# adc_mcp3914.net
KiCad netlist of a schematic drawn in Altium Designer
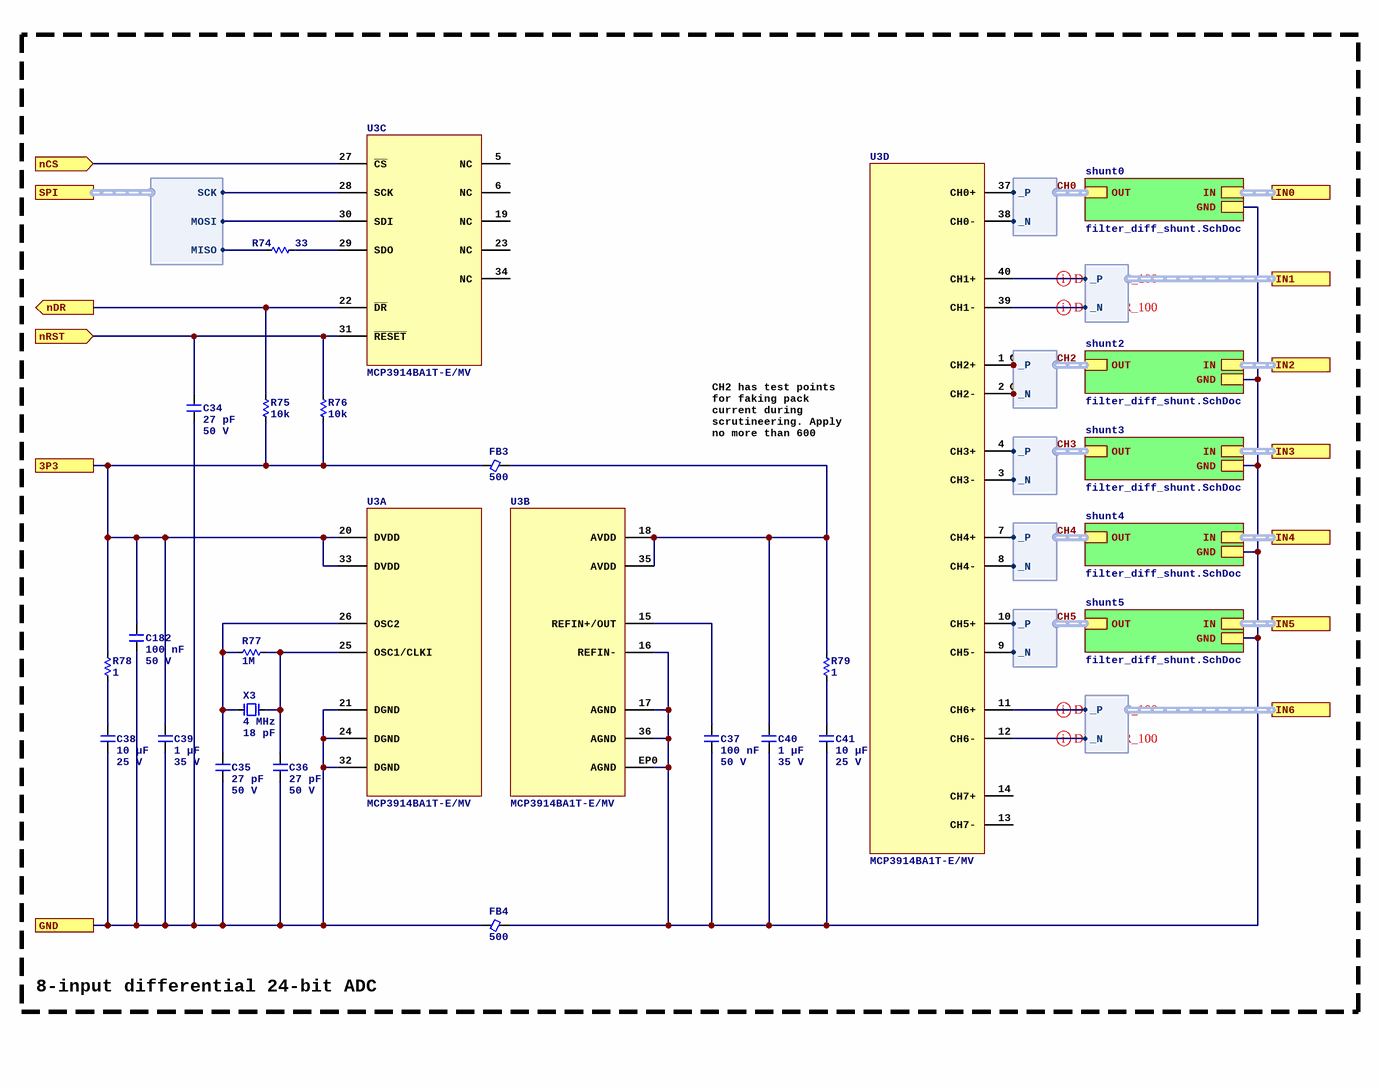
[diagram p0: adc_mcp3914.SchDoc]

(export (version "E")
  (design (tool "Eeschema 10.0.6"))
  (components
    (comp (ref "C34")
      (value "0402CG270J500NT")
      (footprint "C0402")
      (fields
        (field (name "CAPACITANCE") "27 pF")
        (field (name "MANUFACTURER") "FH(Guangdong Fenghua Advanced Tech)")
        (field (name "VOLTAGE RATING") "50 V")
      )
      (libsource (lib "database") (part "__template_cap"))
    )
    (comp (ref "C35")
      (value "0402CG270J500NT")
      (footprint "C0402")
      (fields
        (field (name "CAPACITANCE") "27 pF")
        (field (name "MANUFACTURER") "FH(Guangdong Fenghua Advanced Tech)")
        (field (name "VOLTAGE RATING") "50 V")
      )
      (libsource (lib "database") (part "__template_cap"))
    )
    (comp (ref "C36")
      (value "0402CG270J500NT")
      (footprint "C0402")
      (fields
        (field (name "CAPACITANCE") "27 pF")
        (field (name "MANUFACTURER") "FH(Guangdong Fenghua Advanced Tech)")
        (field (name "VOLTAGE RATING") "50 V")
      )
      (libsource (lib "database") (part "__template_cap"))
    )
    (comp (ref "C37")
      (value "CL05B104KB54PNC")
      (footprint "C0402")
      (fields
        (field (name "CAPACITANCE") "100 nF")
        (field (name "MANUFACTURER") "Samsung Electro-Mechanics")
        (field (name "VOLTAGE RATING") "50 V")
      )
      (libsource (lib "database") (part "__template_cap"))
    )
    (comp (ref "C38")
      (value "CL21B106KAYQNNE")
      (footprint "C0805")
      (fields
        (field (name "CAPACITANCE") "10 µF")
        (field (name "MANUFACTURER") "Samsung Electro-Mechanics")
        (field (name "VOLTAGE RATING") "25 V")
      )
      (libsource (lib "database") (part "__template_cap"))
    )
    (comp (ref "C39")
      (value "GMK107AB7105KAHT")
      (footprint "C0603")
      (fields
        (field (name "CAPACITANCE") "1 µF")
        (field (name "MANUFACTURER") "Taiyo Yuden")
        (field (name "VOLTAGE RATING") "35 V")
      )
      (libsource (lib "database") (part "__template_cap"))
    )
    (comp (ref "C40")
      (value "GMK107AB7105KAHT")
      (footprint "C0603")
      (fields
        (field (name "CAPACITANCE") "1 µF")
        (field (name "MANUFACTURER") "Taiyo Yuden")
        (field (name "VOLTAGE RATING") "35 V")
      )
      (libsource (lib "database") (part "__template_cap"))
    )
    (comp (ref "C41")
      (value "CL21B106KAYQNNE")
      (footprint "C0805")
      (fields
        (field (name "CAPACITANCE") "10 µF")
        (field (name "MANUFACTURER") "Samsung Electro-Mechanics")
        (field (name "VOLTAGE RATING") "25 V")
      )
      (libsource (lib "database") (part "__template_cap"))
    )
    (comp (ref "C182")
      (value "CL05B104KB54PNC")
      (footprint "C0402")
      (fields
        (field (name "CAPACITANCE") "100 nF")
        (field (name "MANUFACTURER") "Samsung Electro-Mechanics")
        (field (name "VOLTAGE RATING") "50 V")
      )
      (libsource (lib "database") (part "__template_cap"))
    )
    (comp (ref "FB3")
      (value "BLM15AX601SN1D")
      (footprint "FB0402")
      (fields (field (name "MANUFACTURER") "Murata Electronics") (field (name "CURRENT RATING (MA)") "500"))
      (libsource (lib "database") (part "__template_fb"))
    )
    (comp (ref "FB4")
      (value "BLM15AX601SN1D")
      (footprint "FB0402")
      (fields (field (name "MANUFACTURER") "Murata Electronics") (field (name "CURRENT RATING (MA)") "500"))
      (libsource (lib "database") (part "__template_fb"))
    )
    (comp (ref "R74")
      (value "33")
      (footprint "R0402")
      (fields
        (field (name "TOLERANCE") "1%")
        (field (name "MANUFACTURER PART NUMBER") "0402WGF330JTCE")
        (field (name "MANUFACTURER") "UNI-ROYAL(Uniroyal Elec)")
      )
      (libsource (lib "database") (part "__template_resistor"))
    )
    (comp (ref "R75")
      (value "10k")
      (footprint "R0402")
      (fields
        (field (name "TOLERANCE") "1%")
        (field (name "MANUFACTURER PART NUMBER") "0402WGF1002TCE")
        (field (name "MANUFACTURER") "UNI-ROYAL(Uniroyal Elec)")
      )
      (libsource (lib "database") (part "__template_resistor"))
    )
    (comp (ref "R76")
      (value "10k")
      (footprint "R0402")
      (fields
        (field (name "TOLERANCE") "1%")
        (field (name "MANUFACTURER PART NUMBER") "0402WGF1002TCE")
        (field (name "MANUFACTURER") "UNI-ROYAL(Uniroyal Elec)")
      )
      (libsource (lib "database") (part "__template_resistor"))
    )
    (comp (ref "R77")
      (value "1M")
      (footprint "R0402")
      (fields
        (field (name "TOLERANCE") "1%")
        (field (name "MANUFACTURER PART NUMBER") "0402WGF1004TCE")
        (field (name "MANUFACTURER") "UNI-ROYAL(Uniroyal Elec)")
      )
      (libsource (lib "database") (part "__template_resistor"))
    )
    (comp (ref "R78")
      (value "1")
      (footprint "R0402")
      (fields
        (field (name "TOLERANCE") "1%")
        (field (name "MANUFACTURER PART NUMBER") "CRCW04021R00FKED")
        (field (name "MANUFACTURER") "Vishay Intertech")
      )
      (libsource (lib "database") (part "__template_resistor"))
    )
    (comp (ref "R79")
      (value "1")
      (footprint "R0402")
      (fields
        (field (name "TOLERANCE") "1%")
        (field (name "MANUFACTURER PART NUMBER") "CRCW04021R00FKED")
        (field (name "MANUFACTURER") "Vishay Intertech")
      )
      (libsource (lib "database") (part "__template_resistor"))
    )
    (comp (ref "TP71")
      (value "RH-5000")
      (footprint "TP_RH-5000")
      (description "Red through-hole PCB test point")
      (fields (field (name "MANUFACTURER") "ronghe"))
      (libsource (lib "database") (part "__template_testpoint"))
    )
    (comp (ref "TP72")
      (value "RH-5001")
      (footprint "TP_RH-5001")
      (description "Black through-hole PCB test point")
      (fields (field (name "MANUFACTURER") "ronghe"))
      (libsource (lib "database") (part "__template_testpoint"))
    )
    (comp (ref "U3")
      (value "MCP3914BA1T-E/MV")
      (footprint "MICROCHIP_MV")
      (description "8 Channel AFE 24 Bit 40-UQFN (5x5)")
      (fields (field (name "MANUFACTURER") "Microchip"))
      (libsource (lib "") (part "MCP3914BA1T-E/MV_1"))
    )
    (comp (ref "X3")
      (value "ABLS2-4.000MHZ-D4Y-T")
      (footprint "XTAL_HC49US_SMD")
      (description "CRYSTAL 4.000 MHZ 18PF SMD")
      (fields
        (field (name "MANUFACTURER") "Abracon LLC")
        (field (name "FREQUENCY") "4 MHz")
        (field (name "CAPACITANCE") "18 pF")
      )
      (libsource (lib "database") (part "__template_crystal_2pin"))
    )
  )
  (nets
    (net (code "13") (name "/3P3") (class "Default")
      (node (ref "C182") (pin "1") (pintype "passive"))
      (node (ref "C39") (pin "1") (pintype "passive"))
      (node (ref "FB3") (pin "1") (pintype "passive"))
      (node (ref "R75") (pin "2") (pintype "passive"))
      (node (ref "R76") (pin "2") (pintype "passive"))
      (node (ref "R78") (pin "2") (pintype "passive"))
      (node (ref "U3") (pin "20") (pinfunction "DVDD_20") (pintype "passive"))
      (node (ref "U3") (pin "33") (pinfunction "DVDD_33") (pintype "passive"))
    )
    (net (code "19") (name "/GND") (class "Default")
      (node (ref "C182") (pin "2") (pintype "passive"))
      (node (ref "C34") (pin "2") (pintype "passive"))
      (node (ref "C35") (pin "2") (pintype "passive"))
      (node (ref "C36") (pin "2") (pintype "passive"))
      (node (ref "C38") (pin "2") (pintype "passive"))
      (node (ref "C39") (pin "2") (pintype "passive"))
      (node (ref "FB4") (pin "1") (pintype "passive"))
      (node (ref "U3") (pin "21") (pinfunction "DGND_21") (pintype "passive"))
      (node (ref "U3") (pin "24") (pinfunction "DGND_24") (pintype "passive"))
      (node (ref "U3") (pin "32") (pinfunction "DGND_32") (pintype "passive"))
    )
    (net (code "20") (name "/GND_1") (class "Default")
      (node (ref "C37") (pin "2") (pintype "passive"))
      (node (ref "C40") (pin "2") (pintype "passive"))
      (node (ref "C41") (pin "2") (pintype "passive"))
      (node (ref "FB4") (pin "2") (pintype "passive"))
      (node (ref "U3") (pin "16") (pinfunction "REFIN-_16") (pintype "passive"))
      (node (ref "U3") (pin "17") (pinfunction "AGND_17") (pintype "passive"))
      (node (ref "U3") (pin "36") (pinfunction "AGND_36") (pintype "passive"))
      (node (ref "U3") (pin "EP0") (pinfunction "AGND_EP0") (pintype "passive"))
    )
    (net (code "26") (name "/MISO") (class "Default") (node (ref "R74") (pin "2") (pintype "passive")))
    (net (code "27") (name "/MOSI") (class "Default")
      (node (ref "U3") (pin "30") (pinfunction "SDI_30") (pintype "passive"))
    )
    (net (code "28") (name "/SCK") (class "Default")
      (node (ref "U3") (pin "28") (pinfunction "SCK_28") (pintype "passive"))
    )
    (net (code "29") (name "/nCS") (class "Default")
      (node (ref "U3") (pin "27") (pinfunction "~{CS}_27") (pintype "passive"))
    )
    (net (code "30") (name "/nDR") (class "Default")
      (node (ref "R75") (pin "1") (pintype "passive"))
      (node (ref "U3") (pin "22") (pinfunction "~{DR}_22") (pintype "passive"))
    )
    (net (code "31") (name "/nRST") (class "Default")
      (node (ref "C34") (pin "1") (pintype "passive"))
      (node (ref "R76") (pin "1") (pintype "passive"))
      (node (ref "U3") (pin "31") (pinfunction "~{RESET}_31") (pintype "passive"))
    )
    (net (code "34") (name "Net-(C38-Pad1)") (class "Default")
      (node (ref "C38") (pin "1") (pintype "passive"))
      (node (ref "R78") (pin "1") (pintype "passive"))
    )
    (net (code "35") (name "Net-(C40-Pad1)") (class "Default")
      (node (ref "C40") (pin "1") (pintype "passive"))
      (node (ref "FB3") (pin "2") (pintype "passive"))
      (node (ref "R79") (pin "2") (pintype "passive"))
      (node (ref "U3") (pin "18") (pinfunction "AVDD_18") (pintype "passive"))
      (node (ref "U3") (pin "35") (pinfunction "AVDD_35") (pintype "passive"))
    )
    (net (code "36") (name "Net-(C41-Pad1)") (class "Default")
      (node (ref "C41") (pin "1") (pintype "passive"))
      (node (ref "R79") (pin "1") (pintype "passive"))
    )
    (net (code "37") (name "Net-(U3A-OSC1{slash}CLKI)") (class "Default")
      (node (ref "C36") (pin "1") (pintype "passive"))
      (node (ref "R77") (pin "1") (pintype "passive"))
      (node (ref "U3") (pin "25") (pinfunction "OSC1/CLKI_25") (pintype "passive"))
      (node (ref "X3") (pin "1") (pinfunction "1_1") (pintype "passive"))
    )
    (net (code "38") (name "Net-(U3A-OSC2)") (class "Default")
      (node (ref "C35") (pin "1") (pintype "passive"))
      (node (ref "R77") (pin "2") (pintype "passive"))
      (node (ref "U3") (pin "26") (pinfunction "OSC2_26") (pintype "passive"))
      (node (ref "X3") (pin "2") (pinfunction "2_2") (pintype "passive"))
    )
    (net (code "39") (name "Net-(U3B-REFIN+{slash}OUT)") (class "Default")
      (node (ref "C37") (pin "1") (pintype "passive"))
      (node (ref "U3") (pin "15") (pinfunction "REFIN+/OUT_15") (pintype "passive"))
    )
    (net (code "40") (name "Net-(U3C-SDO)") (class "Default")
      (node (ref "R74") (pin "1") (pintype "passive"))
      (node (ref "U3") (pin "29") (pinfunction "SDO_29") (pintype "passive"))
    )
    (net (code "41") (name "Net-(U3D-CH2+)") (class "Default")
      (node (ref "TP71") (pin "1") (pintype "passive"))
      (node (ref "U3") (pin "1") (pinfunction "CH2+_1") (pintype "passive"))
    )
    (net (code "42") (name "Net-(U3D-CH2-)") (class "Default")
      (node (ref "TP72") (pin "1") (pintype "passive"))
      (node (ref "U3") (pin "2") (pinfunction "CH2-_2") (pintype "passive"))
    )
    (net (code "43") (name "unconnected-(U3C-NC-Pad5)") (class "Default")
      (node (ref "U3") (pin "5") (pinfunction "NC_5") (pintype "passive"))
    )
    (net (code "44") (name "unconnected-(U3C-NC-Pad6)") (class "Default")
      (node (ref "U3") (pin "6") (pinfunction "NC_6") (pintype "passive"))
    )
    (net (code "45") (name "unconnected-(U3C-NC-Pad19)") (class "Default")
      (node (ref "U3") (pin "19") (pinfunction "NC_19") (pintype "passive"))
    )
    (net (code "46") (name "unconnected-(U3C-NC-Pad23)") (class "Default")
      (node (ref "U3") (pin "23") (pinfunction "NC_23") (pintype "passive"))
    )
    (net (code "47") (name "unconnected-(U3C-NC-Pad34)") (class "Default")
      (node (ref "U3") (pin "34") (pinfunction "NC_34") (pintype "passive"))
    )
    (net (code "48") (name "unconnected-(U3D-CH0+-Pad37)") (class "Default")
      (node (ref "U3") (pin "37") (pinfunction "CH0+_37") (pintype "passive"))
    )
    (net (code "49") (name "unconnected-(U3D-CH0--Pad38)") (class "Default")
      (node (ref "U3") (pin "38") (pinfunction "CH0-_38") (pintype "passive"))
    )
    (net (code "50") (name "unconnected-(U3D-CH1+-Pad40)") (class "Default")
      (node (ref "U3") (pin "40") (pinfunction "CH1+_40") (pintype "passive"))
    )
    (net (code "51") (name "unconnected-(U3D-CH1--Pad39)") (class "Default")
      (node (ref "U3") (pin "39") (pinfunction "CH1-_39") (pintype "passive"))
    )
    (net (code "52") (name "unconnected-(U3D-CH3+-Pad4)") (class "Default")
      (node (ref "U3") (pin "4") (pinfunction "CH3+_4") (pintype "passive"))
    )
    (net (code "53") (name "unconnected-(U3D-CH3--Pad3)") (class "Default")
      (node (ref "U3") (pin "3") (pinfunction "CH3-_3") (pintype "passive"))
    )
    (net (code "54") (name "unconnected-(U3D-CH4+-Pad7)") (class "Default")
      (node (ref "U3") (pin "7") (pinfunction "CH4+_7") (pintype "passive"))
    )
    (net (code "55") (name "unconnected-(U3D-CH4--Pad8)") (class "Default")
      (node (ref "U3") (pin "8") (pinfunction "CH4-_8") (pintype "passive"))
    )
    (net (code "56") (name "unconnected-(U3D-CH5+-Pad10)") (class "Default")
      (node (ref "U3") (pin "10") (pinfunction "CH5+_10") (pintype "passive"))
    )
    (net (code "57") (name "unconnected-(U3D-CH5--Pad9)") (class "Default")
      (node (ref "U3") (pin "9") (pinfunction "CH5-_9") (pintype "passive"))
    )
    (net (code "58") (name "unconnected-(U3D-CH6+-Pad11)") (class "Default")
      (node (ref "U3") (pin "11") (pinfunction "CH6+_11") (pintype "passive"))
    )
    (net (code "59") (name "unconnected-(U3D-CH6--Pad12)") (class "Default")
      (node (ref "U3") (pin "12") (pinfunction "CH6-_12") (pintype "passive"))
    )
    (net (code "60") (name "unconnected-(U3D-CH7+-Pad14)") (class "Default")
      (node (ref "U3") (pin "14") (pinfunction "CH7+_14") (pintype "passive"))
    )
    (net (code "61") (name "unconnected-(U3D-CH7--Pad13)") (class "Default")
      (node (ref "U3") (pin "13") (pinfunction "CH7-_13") (pintype "passive"))
    )
  )
)
